# SmartMCU_sch.net
KiCad netlist of a schematic drawn in Altium Designer
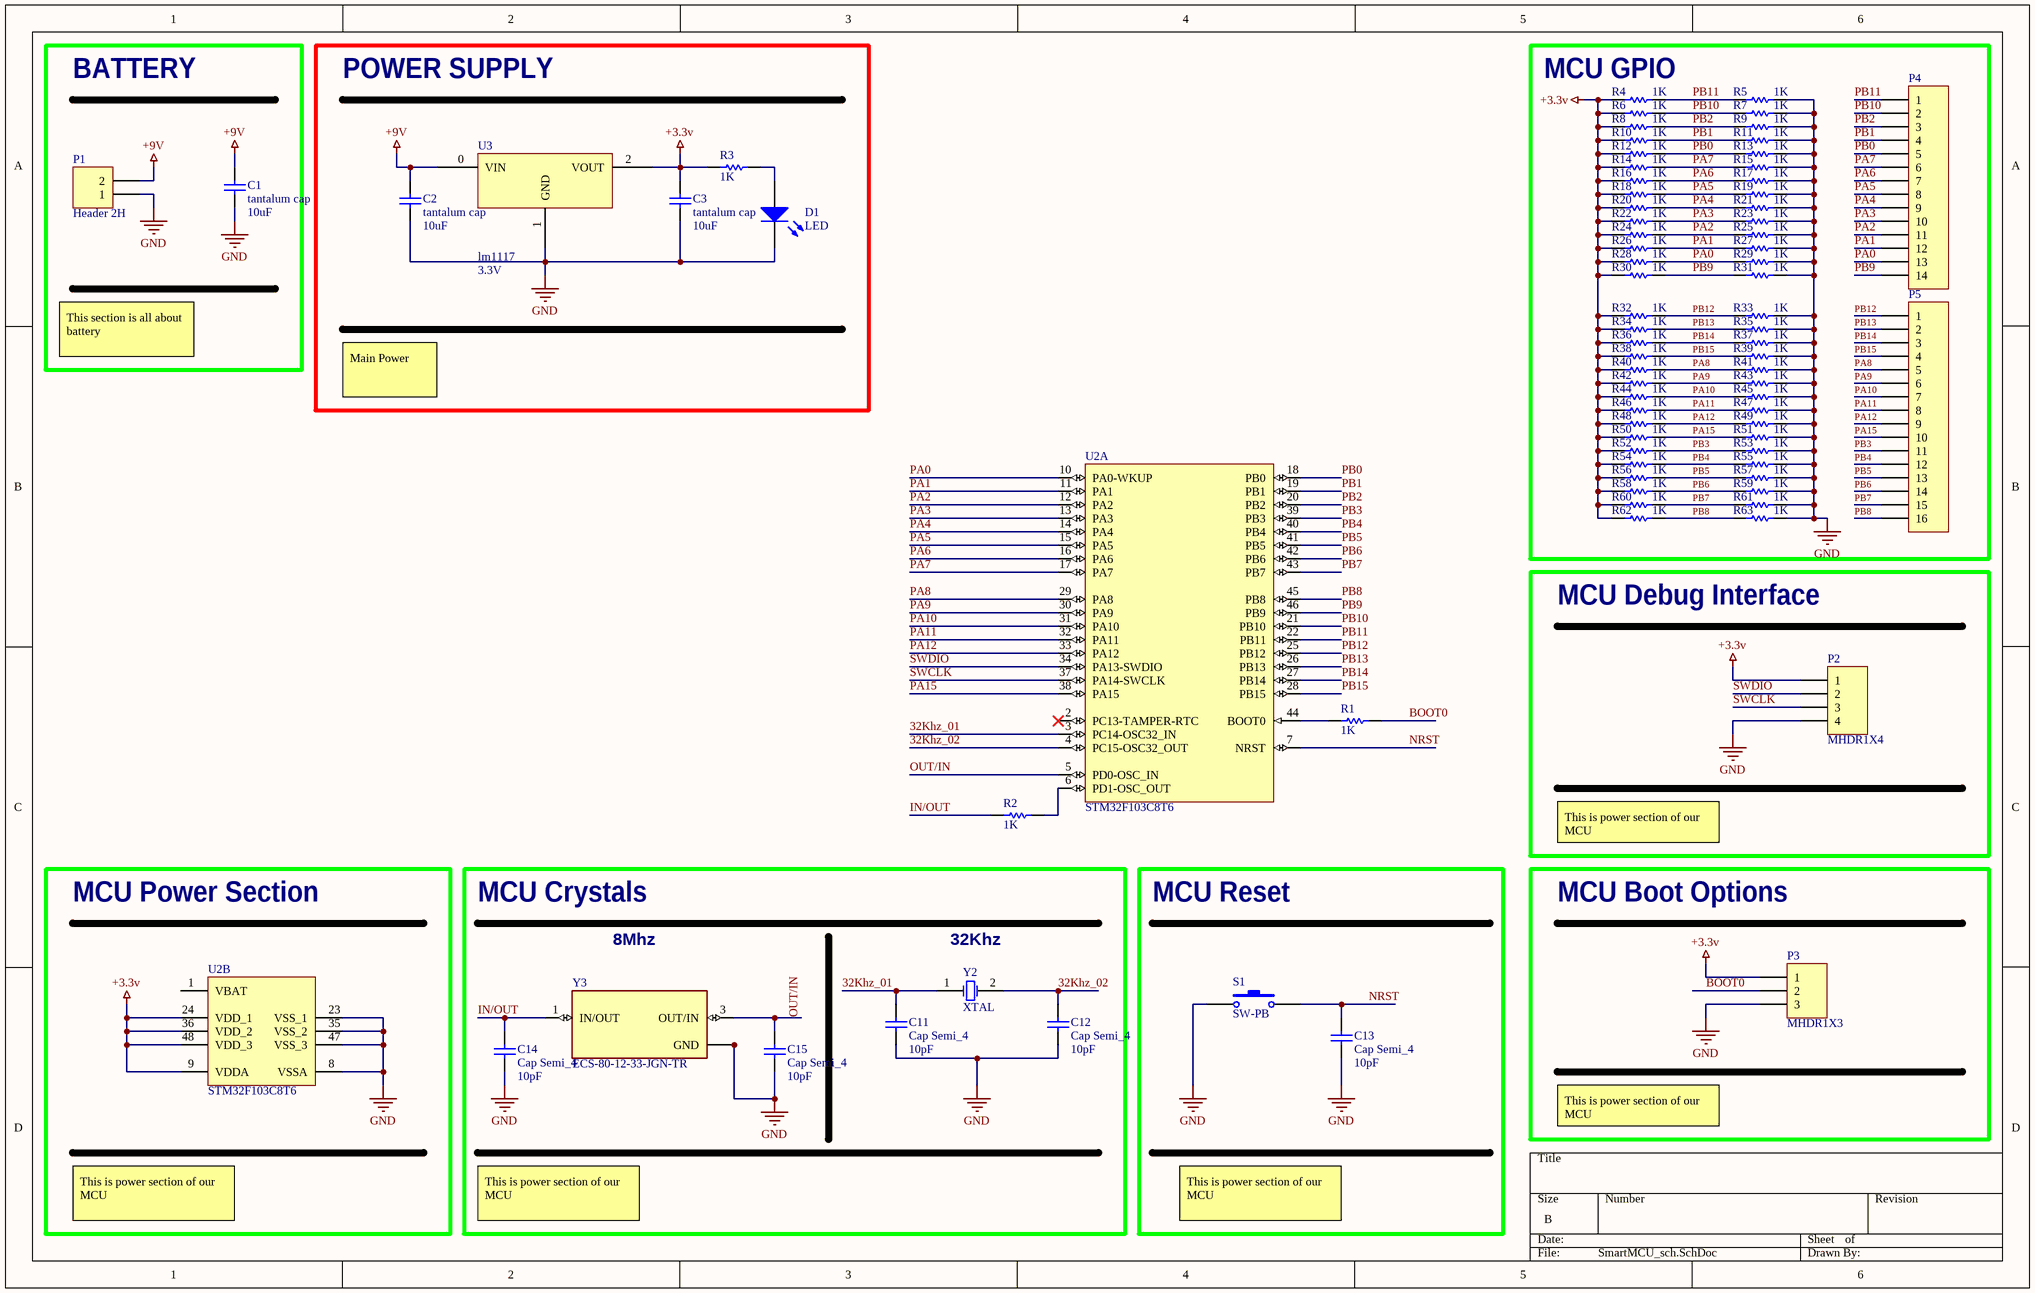
[diagram p0: SmartMCU_sch.SchDoc]

(export (version "E")
  (design (tool "Eeschema 10.0.6"))
  (components
    (comp (ref "C1")
      (value "tantalum cap")
      (footprint "C1206tancap")
      (description "Capacitor (Semiconductor SIM Model)")
      (fields (field (name "ALTIUM_VALUE") "10uF") (field (name "PUBLISHER") "Altium Limited"))
      (libsource (lib "smartmcu") (part "Cap Semi_5"))
    )
    (comp (ref "C2")
      (value "tantalum cap")
      (footprint "C1206tancap")
      (description "Capacitor (Semiconductor SIM Model)")
      (fields (field (name "ALTIUM_VALUE") "10uF") (field (name "PUBLISHER") "Altium Limited"))
      (libsource (lib "smartmcu") (part "Cap Semi_5"))
    )
    (comp (ref "C3")
      (value "tantalum cap")
      (footprint "C1206tancap")
      (description "Capacitor (Semiconductor SIM Model)")
      (fields (field (name "ALTIUM_VALUE") "10uF") (field (name "PUBLISHER") "Altium Limited"))
      (libsource (lib "smartmcu") (part "Cap Semi_5"))
    )
    (comp (ref "C11")
      (value "Cap Semi_4")
      (footprint "0402cap")
      (description "Capacitor (Semiconductor SIM Model)")
      (fields (field (name "ALTIUM_VALUE") "10pF") (field (name "PUBLISHER") "Altium Limited"))
      (libsource (lib "smartmcu") (part "Cap Semi_4"))
    )
    (comp (ref "C12")
      (value "Cap Semi_4")
      (footprint "0402cap")
      (description "Capacitor (Semiconductor SIM Model)")
      (fields (field (name "ALTIUM_VALUE") "10pF") (field (name "PUBLISHER") "Altium Limited"))
      (libsource (lib "smartmcu") (part "Cap Semi_4"))
    )
    (comp (ref "C13")
      (value "Cap Semi_4")
      (footprint "0402cap")
      (description "Capacitor (Semiconductor SIM Model)")
      (fields (field (name "ALTIUM_VALUE") "10pF") (field (name "PUBLISHER") "Altium Limited"))
      (libsource (lib "smartmcu") (part "Cap Semi_4"))
    )
    (comp (ref "C14")
      (value "Cap Semi_4")
      (footprint "0402cap")
      (description "Capacitor (Semiconductor SIM Model)")
      (fields (field (name "ALTIUM_VALUE") "10pF") (field (name "PUBLISHER") "Altium Limited"))
      (libsource (lib "smartmcu") (part "Cap Semi_4"))
    )
    (comp (ref "C15")
      (value "Cap Semi_4")
      (footprint "0402cap")
      (description "Capacitor (Semiconductor SIM Model)")
      (fields (field (name "ALTIUM_VALUE") "10pF") (field (name "PUBLISHER") "Altium Limited"))
      (libsource (lib "smartmcu") (part "Cap Semi_4"))
    )
    (comp (ref "D1")
      (value "LED")
      (footprint "MY_LED_0805")
      (description "Typical INFRARED GaAs LED")
      (fields (field (name "ASID PART NUMBER") "LED-AS"))
      (libsource (lib "Mylib+Rev+4") (part "LED"))
    )
    (comp (ref "P1")
      (value "Header 2H")
      (footprint "HDR1X2H")
      (description "Header, 2-Pin, Right Angle")
      (fields (field (name "VOLTAGE") "9V") (field (name "PUBLISHER") "Altium Limited"))
      (libsource (lib "Miscellaneous Connectors") (part "Header 2H"))
    )
    (comp (ref "P2")
      (value "MHDR1X4")
      (footprint "MHDR1X4body")
      (description "Header, 4-Pin")
      (fields (field (name "PUBLISHER") "Altium Limited"))
      (libsource (lib "smartmcu") (part "MHDR1X4"))
    )
    (comp (ref "P3")
      (value "MHDR1X3")
      (footprint "MHDR1X3body")
      (description "Header, 3-Pin")
      (fields (field (name "PUBLISHER") "Altium Limited"))
      (libsource (lib "smartmcu") (part "MHDR1X3"))
    )
    (comp (ref "P4")
      (value "Header 14")
      (footprint "My_1X14")
      (description "Header, 14-Pin")
      (fields (field (name "ASID PART NUMBER") "Header 14-AS"))
      (libsource (lib "Mylib+Rev+4") (part "Header 14"))
    )
    (comp (ref "P5")
      (value "Header 16")
      (footprint "My_1X16")
      (description "Header, 16-Pin")
      (fields (field (name "ASID PART NUMBER") "Header 16-AS"))
      (libsource (lib "Mylib+Rev+4") (part "Header 16"))
    )
    (comp (ref "R1")
      (value "1K")
      (footprint "MY_0603")
      (description "Standard resistor")
      (fields (field (name "ASID PART NUMBER") "Res-AS"))
      (libsource (lib "Mylib+Rev+4") (part "Res"))
    )
    (comp (ref "R2")
      (value "1K")
      (footprint "MY_0402")
      (description "Standard resistor")
      (fields (field (name "ASID PART NUMBER") "Res-AS"))
      (libsource (lib "Mylib+Rev+4") (part "Res"))
    )
    (comp (ref "R3")
      (value "1K")
      (footprint "MY_0805")
      (description "Standard resistor")
      (fields (field (name "ASID PART NUMBER") "Res-AS"))
      (libsource (lib "Mylib+Rev+4") (part "Res"))
    )
    (comp (ref "R4")
      (value "1K")
      (footprint "MY_0603")
      (description "Standard resistor")
      (fields (field (name "ASID PART NUMBER") "Res-AS"))
      (libsource (lib "Mylib+Rev+4") (part "Res"))
    )
    (comp (ref "R5")
      (value "1K")
      (footprint "MY_0603")
      (description "Standard resistor")
      (fields (field (name "ASID PART NUMBER") "Res-AS"))
      (libsource (lib "Mylib+Rev+4") (part "Res"))
    )
    (comp (ref "R6")
      (value "1K")
      (footprint "MY_0603")
      (description "Standard resistor")
      (fields (field (name "ASID PART NUMBER") "Res-AS"))
      (libsource (lib "Mylib+Rev+4") (part "Res"))
    )
    (comp (ref "R7")
      (value "1K")
      (footprint "MY_0603")
      (description "Standard resistor")
      (fields (field (name "ASID PART NUMBER") "Res-AS"))
      (libsource (lib "Mylib+Rev+4") (part "Res"))
    )
    (comp (ref "R8")
      (value "1K")
      (footprint "MY_0603")
      (description "Standard resistor")
      (fields (field (name "ASID PART NUMBER") "Res-AS"))
      (libsource (lib "Mylib+Rev+4") (part "Res"))
    )
    (comp (ref "R9")
      (value "1K")
      (footprint "MY_0603")
      (description "Standard resistor")
      (fields (field (name "ASID PART NUMBER") "Res-AS"))
      (libsource (lib "Mylib+Rev+4") (part "Res"))
    )
    (comp (ref "R10")
      (value "1K")
      (footprint "MY_0603")
      (description "Standard resistor")
      (fields (field (name "ASID PART NUMBER") "Res-AS"))
      (libsource (lib "Mylib+Rev+4") (part "Res"))
    )
    (comp (ref "R11")
      (value "1K")
      (footprint "MY_0603")
      (description "Standard resistor")
      (fields (field (name "ASID PART NUMBER") "Res-AS"))
      (libsource (lib "Mylib+Rev+4") (part "Res"))
    )
    (comp (ref "R12")
      (value "1K")
      (footprint "MY_0603")
      (description "Standard resistor")
      (fields (field (name "ASID PART NUMBER") "Res-AS"))
      (libsource (lib "Mylib+Rev+4") (part "Res"))
    )
    (comp (ref "R13")
      (value "1K")
      (footprint "MY_0603")
      (description "Standard resistor")
      (fields (field (name "ASID PART NUMBER") "Res-AS"))
      (libsource (lib "Mylib+Rev+4") (part "Res"))
    )
    (comp (ref "R14")
      (value "1K")
      (footprint "MY_0603")
      (description "Standard resistor")
      (fields (field (name "ASID PART NUMBER") "Res-AS"))
      (libsource (lib "Mylib+Rev+4") (part "Res"))
    )
    (comp (ref "R15")
      (value "1K")
      (footprint "MY_0603")
      (description "Standard resistor")
      (fields (field (name "ASID PART NUMBER") "Res-AS"))
      (libsource (lib "Mylib+Rev+4") (part "Res"))
    )
    (comp (ref "R16")
      (value "1K")
      (footprint "MY_0603")
      (description "Standard resistor")
      (fields (field (name "ASID PART NUMBER") "Res-AS"))
      (libsource (lib "Mylib+Rev+4") (part "Res"))
    )
    (comp (ref "R17")
      (value "1K")
      (footprint "MY_0603")
      (description "Standard resistor")
      (fields (field (name "ASID PART NUMBER") "Res-AS"))
      (libsource (lib "Mylib+Rev+4") (part "Res"))
    )
    (comp (ref "R18")
      (value "1K")
      (footprint "MY_0603")
      (description "Standard resistor")
      (fields (field (name "ASID PART NUMBER") "Res-AS"))
      (libsource (lib "Mylib+Rev+4") (part "Res"))
    )
    (comp (ref "R19")
      (value "1K")
      (footprint "MY_0603")
      (description "Standard resistor")
      (fields (field (name "ASID PART NUMBER") "Res-AS"))
      (libsource (lib "Mylib+Rev+4") (part "Res"))
    )
    (comp (ref "R20")
      (value "1K")
      (footprint "MY_0603")
      (description "Standard resistor")
      (fields (field (name "ASID PART NUMBER") "Res-AS"))
      (libsource (lib "Mylib+Rev+4") (part "Res"))
    )
    (comp (ref "R21")
      (value "1K")
      (footprint "MY_0603")
      (description "Standard resistor")
      (fields (field (name "ASID PART NUMBER") "Res-AS"))
      (libsource (lib "Mylib+Rev+4") (part "Res"))
    )
    (comp (ref "R22")
      (value "1K")
      (footprint "MY_0603")
      (description "Standard resistor")
      (fields (field (name "ASID PART NUMBER") "Res-AS"))
      (libsource (lib "Mylib+Rev+4") (part "Res"))
    )
    (comp (ref "R23")
      (value "1K")
      (footprint "MY_0603")
      (description "Standard resistor")
      (fields (field (name "ASID PART NUMBER") "Res-AS"))
      (libsource (lib "Mylib+Rev+4") (part "Res"))
    )
    (comp (ref "R24")
      (value "1K")
      (footprint "MY_0603")
      (description "Standard resistor")
      (fields (field (name "ASID PART NUMBER") "Res-AS"))
      (libsource (lib "Mylib+Rev+4") (part "Res"))
    )
    (comp (ref "R25")
      (value "1K")
      (footprint "MY_0603")
      (description "Standard resistor")
      (fields (field (name "ASID PART NUMBER") "Res-AS"))
      (libsource (lib "Mylib+Rev+4") (part "Res"))
    )
    (comp (ref "R26")
      (value "1K")
      (footprint "MY_0603")
      (description "Standard resistor")
      (fields (field (name "ASID PART NUMBER") "Res-AS"))
      (libsource (lib "Mylib+Rev+4") (part "Res"))
    )
    (comp (ref "R27")
      (value "1K")
      (footprint "MY_0603")
      (description "Standard resistor")
      (fields (field (name "ASID PART NUMBER") "Res-AS"))
      (libsource (lib "Mylib+Rev+4") (part "Res"))
    )
    (comp (ref "R28")
      (value "1K")
      (footprint "MY_0603")
      (description "Standard resistor")
      (fields (field (name "ASID PART NUMBER") "Res-AS"))
      (libsource (lib "Mylib+Rev+4") (part "Res"))
    )
    (comp (ref "R29")
      (value "1K")
      (footprint "MY_0603")
      (description "Standard resistor")
      (fields (field (name "ASID PART NUMBER") "Res-AS"))
      (libsource (lib "Mylib+Rev+4") (part "Res"))
    )
    (comp (ref "R30")
      (value "1K")
      (footprint "MY_0603")
      (description "Standard resistor")
      (fields (field (name "ASID PART NUMBER") "Res-AS"))
      (libsource (lib "Mylib+Rev+4") (part "Res"))
    )
    (comp (ref "R31")
      (value "1K")
      (footprint "MY_0603")
      (description "Standard resistor")
      (fields (field (name "ASID PART NUMBER") "Res-AS"))
      (libsource (lib "Mylib+Rev+4") (part "Res"))
    )
    (comp (ref "R32")
      (value "1K")
      (footprint "MY_0603")
      (description "Standard resistor")
      (fields (field (name "ASID PART NUMBER") "Res-AS"))
      (libsource (lib "Mylib+Rev+4") (part "Res"))
    )
    (comp (ref "R33")
      (value "1K")
      (footprint "MY_0603")
      (description "Standard resistor")
      (fields (field (name "ASID PART NUMBER") "Res-AS"))
      (libsource (lib "Mylib+Rev+4") (part "Res"))
    )
    (comp (ref "R34")
      (value "1K")
      (footprint "MY_0603")
      (description "Standard resistor")
      (fields (field (name "ASID PART NUMBER") "Res-AS"))
      (libsource (lib "Mylib+Rev+4") (part "Res"))
    )
    (comp (ref "R35")
      (value "1K")
      (footprint "MY_0603")
      (description "Standard resistor")
      (fields (field (name "ASID PART NUMBER") "Res-AS"))
      (libsource (lib "Mylib+Rev+4") (part "Res"))
    )
    (comp (ref "R36")
      (value "1K")
      (footprint "MY_0603")
      (description "Standard resistor")
      (fields (field (name "ASID PART NUMBER") "Res-AS"))
      (libsource (lib "Mylib+Rev+4") (part "Res"))
    )
    (comp (ref "R37")
      (value "1K")
      (footprint "MY_0603")
      (description "Standard resistor")
      (fields (field (name "ASID PART NUMBER") "Res-AS"))
      (libsource (lib "Mylib+Rev+4") (part "Res"))
    )
    (comp (ref "R38")
      (value "1K")
      (footprint "MY_0603")
      (description "Standard resistor")
      (fields (field (name "ASID PART NUMBER") "Res-AS"))
      (libsource (lib "Mylib+Rev+4") (part "Res"))
    )
    (comp (ref "R39")
      (value "1K")
      (footprint "MY_0603")
      (description "Standard resistor")
      (fields (field (name "ASID PART NUMBER") "Res-AS"))
      (libsource (lib "Mylib+Rev+4") (part "Res"))
    )
    (comp (ref "R40")
      (value "1K")
      (footprint "MY_0603")
      (description "Standard resistor")
      (fields (field (name "ASID PART NUMBER") "Res-AS"))
      (libsource (lib "Mylib+Rev+4") (part "Res"))
    )
    (comp (ref "R41")
      (value "1K")
      (footprint "MY_0603")
      (description "Standard resistor")
      (fields (field (name "ASID PART NUMBER") "Res-AS"))
      (libsource (lib "Mylib+Rev+4") (part "Res"))
    )
    (comp (ref "R42")
      (value "1K")
      (footprint "MY_0603")
      (description "Standard resistor")
      (fields (field (name "ASID PART NUMBER") "Res-AS"))
      (libsource (lib "Mylib+Rev+4") (part "Res"))
    )
    (comp (ref "R43")
      (value "1K")
      (footprint "MY_0603")
      (description "Standard resistor")
      (fields (field (name "ASID PART NUMBER") "Res-AS"))
      (libsource (lib "Mylib+Rev+4") (part "Res"))
    )
    (comp (ref "R44")
      (value "1K")
      (footprint "MY_0603")
      (description "Standard resistor")
      (fields (field (name "ASID PART NUMBER") "Res-AS"))
      (libsource (lib "Mylib+Rev+4") (part "Res"))
    )
    (comp (ref "R45")
      (value "1K")
      (footprint "MY_0603")
      (description "Standard resistor")
      (fields (field (name "ASID PART NUMBER") "Res-AS"))
      (libsource (lib "Mylib+Rev+4") (part "Res"))
    )
    (comp (ref "R46")
      (value "1K")
      (footprint "MY_0603")
      (description "Standard resistor")
      (fields (field (name "ASID PART NUMBER") "Res-AS"))
      (libsource (lib "Mylib+Rev+4") (part "Res"))
    )
    (comp (ref "R47")
      (value "1K")
      (footprint "MY_0603")
      (description "Standard resistor")
      (fields (field (name "ASID PART NUMBER") "Res-AS"))
      (libsource (lib "Mylib+Rev+4") (part "Res"))
    )
    (comp (ref "R48")
      (value "1K")
      (footprint "MY_0603")
      (description "Standard resistor")
      (fields (field (name "ASID PART NUMBER") "Res-AS"))
      (libsource (lib "Mylib+Rev+4") (part "Res"))
    )
    (comp (ref "R49")
      (value "1K")
      (footprint "MY_0603")
      (description "Standard resistor")
      (fields (field (name "ASID PART NUMBER") "Res-AS"))
      (libsource (lib "Mylib+Rev+4") (part "Res"))
    )
    (comp (ref "R50")
      (value "1K")
      (footprint "MY_0603")
      (description "Standard resistor")
      (fields (field (name "ASID PART NUMBER") "Res-AS"))
      (libsource (lib "Mylib+Rev+4") (part "Res"))
    )
    (comp (ref "R51")
      (value "1K")
      (footprint "MY_0603")
      (description "Standard resistor")
      (fields (field (name "ASID PART NUMBER") "Res-AS"))
      (libsource (lib "Mylib+Rev+4") (part "Res"))
    )
    (comp (ref "R52")
      (value "1K")
      (footprint "MY_0603")
      (description "Standard resistor")
      (fields (field (name "ASID PART NUMBER") "Res-AS"))
      (libsource (lib "Mylib+Rev+4") (part "Res"))
    )
    (comp (ref "R53")
      (value "1K")
      (footprint "MY_0603")
      (description "Standard resistor")
      (fields (field (name "ASID PART NUMBER") "Res-AS"))
      (libsource (lib "Mylib+Rev+4") (part "Res"))
    )
    (comp (ref "R54")
      (value "1K")
      (footprint "MY_0603")
      (description "Standard resistor")
      (fields (field (name "ASID PART NUMBER") "Res-AS"))
      (libsource (lib "Mylib+Rev+4") (part "Res"))
    )
    (comp (ref "R55")
      (value "1K")
      (footprint "MY_0603")
      (description "Standard resistor")
      (fields (field (name "ASID PART NUMBER") "Res-AS"))
      (libsource (lib "Mylib+Rev+4") (part "Res"))
    )
    (comp (ref "R56")
      (value "1K")
      (footprint "MY_0603")
      (description "Standard resistor")
      (fields (field (name "ASID PART NUMBER") "Res-AS"))
      (libsource (lib "Mylib+Rev+4") (part "Res"))
    )
    (comp (ref "R57")
      (value "1K")
      (footprint "MY_0603")
      (description "Standard resistor")
      (fields (field (name "ASID PART NUMBER") "Res-AS"))
      (libsource (lib "Mylib+Rev+4") (part "Res"))
    )
    (comp (ref "R58")
      (value "1K")
      (footprint "MY_0603")
      (description "Standard resistor")
      (fields (field (name "ASID PART NUMBER") "Res-AS"))
      (libsource (lib "Mylib+Rev+4") (part "Res"))
    )
    (comp (ref "R59")
      (value "1K")
      (footprint "MY_0603")
      (description "Standard resistor")
      (fields (field (name "ASID PART NUMBER") "Res-AS"))
      (libsource (lib "Mylib+Rev+4") (part "Res"))
    )
    (comp (ref "R60")
      (value "1K")
      (footprint "MY_0603")
      (description "Standard resistor")
      (fields (field (name "ASID PART NUMBER") "Res-AS"))
      (libsource (lib "Mylib+Rev+4") (part "Res"))
    )
    (comp (ref "R61")
      (value "1K")
      (footprint "MY_0603")
      (description "Standard resistor")
      (fields (field (name "ASID PART NUMBER") "Res-AS"))
      (libsource (lib "Mylib+Rev+4") (part "Res"))
    )
    (comp (ref "R62")
      (value "1K")
      (footprint "MY_0603")
      (description "Standard resistor")
      (fields (field (name "ASID PART NUMBER") "Res-AS"))
      (libsource (lib "Mylib+Rev+4") (part "Res"))
    )
    (comp (ref "R63")
      (value "1K")
      (footprint "MY_0603")
      (description "Standard resistor")
      (fields (field (name "ASID PART NUMBER") "Res-AS"))
      (libsource (lib "Mylib+Rev+4") (part "Res"))
    )
    (comp (ref "S1")
      (value "SW-PB")
      (footprint "SPST-2_body")
      (description "Switch")
      (fields (field (name "PUBLISHER") "Altium Limited"))
      (libsource (lib "smartmcu") (part "SW-PB"))
    )
    (comp (ref "U2")
      (value "STM32F103C8T6")
      (footprint "STM-LQFP48_L")
      (libsource (lib "Altium Content Vault") (part "MC-ARM-STM32F103X8_B-SQ48"))
    )
    (comp (ref "U3")
      (value "lm1117")
      (footprint "4-Pin SOT")
      (fields (field (name "OUTPUT VOLTAG") "3.3V"))
      (libsource (lib "smartmcu") (part "lm1117"))
    )
    (comp (ref "Y2")
      (value "XTAL")
      (footprint "32768")
      (description "Crystal Oscillator")
      (fields (field (name "PUBLISHER") "Altium Limited"))
      (libsource (lib "smartmcu") (part "XTAL"))
    )
    (comp (ref "Y3")
      (value "ECS-80-12-33-JGN-TR")
      (footprint "8MHZCrystall")
      (description "8MHz Â±20ppm Crystal 12pF 400 Ohms 4-SMD, No Lead")
      (fields
        (field (name "MF") "ECS Inc.")
        (field (name "BUYPART") "https://www.snapeda.com/parts/ECS-80-12-33-JGN-TR/ECS%20Inc./view-part/4477300/?ref=eda")
      )
      (libsource (lib "smartmcu") (part "ECS-80-12-33-JGN-TR"))
    )
  )
  (nets
    (net (code "1") (name "+3.3v") (class "Default")
      (node (ref "C3") (pin "2") (pinfunction "2_2") (pintype "passive"))
      (node (ref "P2") (pin "1") (pinfunction "1_1") (pintype "passive"))
      (node (ref "P3") (pin "1") (pinfunction "1_1") (pintype "passive"))
      (node (ref "R10") (pin "1") (pinfunction "1_1") (pintype "passive"))
      (node (ref "R12") (pin "1") (pinfunction "1_1") (pintype "passive"))
      (node (ref "R14") (pin "1") (pinfunction "1_1") (pintype "passive"))
      (node (ref "R16") (pin "1") (pinfunction "1_1") (pintype "passive"))
      (node (ref "R18") (pin "1") (pinfunction "1_1") (pintype "passive"))
      (node (ref "R20") (pin "1") (pinfunction "1_1") (pintype "passive"))
      (node (ref "R22") (pin "1") (pinfunction "1_1") (pintype "passive"))
      (node (ref "R24") (pin "1") (pinfunction "1_1") (pintype "passive"))
      (node (ref "R26") (pin "1") (pinfunction "1_1") (pintype "passive"))
      (node (ref "R28") (pin "1") (pinfunction "1_1") (pintype "passive"))
      (node (ref "R3") (pin "1") (pinfunction "1_1") (pintype "passive"))
      (node (ref "R30") (pin "1") (pinfunction "1_1") (pintype "passive"))
      (node (ref "R32") (pin "1") (pinfunction "1_1") (pintype "passive"))
      (node (ref "R34") (pin "1") (pinfunction "1_1") (pintype "passive"))
      (node (ref "R36") (pin "1") (pinfunction "1_1") (pintype "passive"))
      (node (ref "R38") (pin "1") (pinfunction "1_1") (pintype "passive"))
      (node (ref "R4") (pin "1") (pinfunction "1_1") (pintype "passive"))
      (node (ref "R40") (pin "1") (pinfunction "1_1") (pintype "passive"))
      (node (ref "R42") (pin "1") (pinfunction "1_1") (pintype "passive"))
      (node (ref "R44") (pin "1") (pinfunction "1_1") (pintype "passive"))
      (node (ref "R46") (pin "1") (pinfunction "1_1") (pintype "passive"))
      (node (ref "R48") (pin "1") (pinfunction "1_1") (pintype "passive"))
      (node (ref "R50") (pin "1") (pinfunction "1_1") (pintype "passive"))
      (node (ref "R52") (pin "1") (pinfunction "1_1") (pintype "passive"))
      (node (ref "R54") (pin "1") (pinfunction "1_1") (pintype "passive"))
      (node (ref "R56") (pin "1") (pinfunction "1_1") (pintype "passive"))
      (node (ref "R58") (pin "1") (pinfunction "1_1") (pintype "passive"))
      (node (ref "R6") (pin "1") (pinfunction "1_1") (pintype "passive"))
      (node (ref "R60") (pin "1") (pinfunction "1_1") (pintype "passive"))
      (node (ref "R62") (pin "1") (pinfunction "1_1") (pintype "passive"))
      (node (ref "R8") (pin "1") (pinfunction "1_1") (pintype "passive"))
      (node (ref "U2") (pin "24") (pinfunction "VDD_1_24") (pintype "power_in"))
      (node (ref "U2") (pin "36") (pinfunction "VDD_2_36") (pintype "power_in"))
      (node (ref "U2") (pin "48") (pinfunction "VDD_3_48") (pintype "power_in"))
      (node (ref "U2") (pin "9") (pinfunction "VDDA_9") (pintype "power_in"))
      (node (ref "U3") (pin "2") (pinfunction "VOUT_2") (pintype "passive"))
    )
    (net (code "2") (name "+9V") (class "Default")
      (node (ref "C1") (pin "2") (pinfunction "2_2") (pintype "passive"))
      (node (ref "C2") (pin "2") (pinfunction "2_2") (pintype "passive"))
      (node (ref "P1") (pin "2") (pinfunction "2_2") (pintype "passive"))
      (node (ref "U3") (pin "0") (pinfunction "VIN_0") (pintype "passive"))
    )
    (net (code "3") (name "/32Khz_01") (class "Default")
      (node (ref "C11") (pin "1") (pinfunction "1_1") (pintype "passive"))
      (node (ref "U2") (pin "3") (pinfunction "PC14-OSC32_IN_3") (pintype "bidirectional"))
      (node (ref "Y2") (pin "1") (pinfunction "OSC1_1") (pintype "passive"))
    )
    (net (code "4") (name "/32Khz_02") (class "Default")
      (node (ref "C12") (pin "1") (pinfunction "1_1") (pintype "passive"))
      (node (ref "U2") (pin "4") (pinfunction "PC15-OSC32_OUT_4") (pintype "bidirectional"))
      (node (ref "Y2") (pin "2") (pinfunction "OSC2_2") (pintype "passive"))
    )
    (net (code "5") (name "/BOOT0") (class "Default")
      (node (ref "P3") (pin "2") (pinfunction "2_2") (pintype "passive"))
      (node (ref "R1") (pin "2") (pinfunction "2_2") (pintype "passive"))
    )
    (net (code "6") (name "/IN{slash}OUT") (class "Default")
      (node (ref "C14") (pin "1") (pinfunction "1_1") (pintype "passive"))
      (node (ref "R2") (pin "1") (pinfunction "1_1") (pintype "passive"))
      (node (ref "Y3") (pin "1") (pinfunction "IN/OUT_1") (pintype "bidirectional"))
    )
    (net (code "7") (name "/NRST") (class "Default")
      (node (ref "C13") (pin "2") (pinfunction "2_2") (pintype "passive"))
      (node (ref "S1") (pin "2") (pinfunction "2_2") (pintype "passive"))
      (node (ref "U2") (pin "7") (pinfunction "NRST_7") (pintype "bidirectional"))
    )
    (net (code "8") (name "/OUT{slash}IN") (class "Default")
      (node (ref "C15") (pin "1") (pinfunction "1_1") (pintype "passive"))
      (node (ref "U2") (pin "5") (pinfunction "PD0-OSC_IN_5") (pintype "bidirectional"))
      (node (ref "Y3") (pin "3") (pinfunction "OUT/IN_3") (pintype "bidirectional"))
    )
    (net (code "9") (name "/PA0") (class "Default")
      (node (ref "P4") (pin "13") (pinfunction "13_13") (pintype "passive"))
      (node (ref "R28") (pin "2") (pinfunction "2_2") (pintype "passive"))
      (node (ref "R29") (pin "1") (pinfunction "1_1") (pintype "passive"))
      (node (ref "U2") (pin "10") (pinfunction "PA0-WKUP_10") (pintype "bidirectional"))
    )
    (net (code "10") (name "/PA1") (class "Default")
      (node (ref "P4") (pin "12") (pinfunction "12_12") (pintype "passive"))
      (node (ref "R26") (pin "2") (pinfunction "2_2") (pintype "passive"))
      (node (ref "R27") (pin "1") (pinfunction "1_1") (pintype "passive"))
      (node (ref "U2") (pin "11") (pinfunction "PA1_11") (pintype "bidirectional"))
    )
    (net (code "11") (name "/PA2") (class "Default")
      (node (ref "P4") (pin "11") (pinfunction "11_11") (pintype "passive"))
      (node (ref "R24") (pin "2") (pinfunction "2_2") (pintype "passive"))
      (node (ref "R25") (pin "1") (pinfunction "1_1") (pintype "passive"))
      (node (ref "U2") (pin "12") (pinfunction "PA2_12") (pintype "bidirectional"))
    )
    (net (code "12") (name "/PA3") (class "Default")
      (node (ref "P4") (pin "10") (pinfunction "10_10") (pintype "passive"))
      (node (ref "R22") (pin "2") (pinfunction "2_2") (pintype "passive"))
      (node (ref "R23") (pin "1") (pinfunction "1_1") (pintype "passive"))
      (node (ref "U2") (pin "13") (pinfunction "PA3_13") (pintype "bidirectional"))
    )
    (net (code "13") (name "/PA4") (class "Default")
      (node (ref "P4") (pin "9") (pinfunction "9_9") (pintype "passive"))
      (node (ref "R20") (pin "2") (pinfunction "2_2") (pintype "passive"))
      (node (ref "R21") (pin "1") (pinfunction "1_1") (pintype "passive"))
      (node (ref "U2") (pin "14") (pinfunction "PA4_14") (pintype "bidirectional"))
    )
    (net (code "14") (name "/PA5") (class "Default")
      (node (ref "P4") (pin "8") (pinfunction "8_8") (pintype "passive"))
      (node (ref "R18") (pin "2") (pinfunction "2_2") (pintype "passive"))
      (node (ref "R19") (pin "1") (pinfunction "1_1") (pintype "passive"))
      (node (ref "U2") (pin "15") (pinfunction "PA5_15") (pintype "bidirectional"))
    )
    (net (code "15") (name "/PA6") (class "Default")
      (node (ref "P4") (pin "7") (pinfunction "7_7") (pintype "passive"))
      (node (ref "R16") (pin "2") (pinfunction "2_2") (pintype "passive"))
      (node (ref "R17") (pin "1") (pinfunction "1_1") (pintype "passive"))
      (node (ref "U2") (pin "16") (pinfunction "PA6_16") (pintype "bidirectional"))
    )
    (net (code "16") (name "/PA7") (class "Default")
      (node (ref "P4") (pin "6") (pinfunction "6_6") (pintype "passive"))
      (node (ref "R14") (pin "2") (pinfunction "2_2") (pintype "passive"))
      (node (ref "R15") (pin "1") (pinfunction "1_1") (pintype "passive"))
      (node (ref "U2") (pin "17") (pinfunction "PA7_17") (pintype "bidirectional"))
    )
    (net (code "17") (name "/PA8") (class "Default")
      (node (ref "P5") (pin "5") (pinfunction "5_5") (pintype "passive"))
      (node (ref "R40") (pin "2") (pinfunction "2_2") (pintype "passive"))
      (node (ref "R41") (pin "1") (pinfunction "1_1") (pintype "passive"))
      (node (ref "U2") (pin "29") (pinfunction "PA8_29") (pintype "bidirectional"))
    )
    (net (code "18") (name "/PA9") (class "Default")
      (node (ref "P5") (pin "6") (pinfunction "6_6") (pintype "passive"))
      (node (ref "R42") (pin "2") (pinfunction "2_2") (pintype "passive"))
      (node (ref "R43") (pin "1") (pinfunction "1_1") (pintype "passive"))
      (node (ref "U2") (pin "30") (pinfunction "PA9_30") (pintype "bidirectional"))
    )
    (net (code "19") (name "/PA10") (class "Default")
      (node (ref "P5") (pin "7") (pinfunction "7_7") (pintype "passive"))
      (node (ref "R44") (pin "2") (pinfunction "2_2") (pintype "passive"))
      (node (ref "R45") (pin "1") (pinfunction "1_1") (pintype "passive"))
      (node (ref "U2") (pin "31") (pinfunction "PA10_31") (pintype "bidirectional"))
    )
    (net (code "20") (name "/PA11") (class "Default")
      (node (ref "P5") (pin "8") (pinfunction "8_8") (pintype "passive"))
      (node (ref "R46") (pin "2") (pinfunction "2_2") (pintype "passive"))
      (node (ref "R47") (pin "1") (pinfunction "1_1") (pintype "passive"))
      (node (ref "U2") (pin "32") (pinfunction "PA11_32") (pintype "bidirectional"))
    )
    (net (code "21") (name "/PA12") (class "Default")
      (node (ref "P5") (pin "9") (pinfunction "9_9") (pintype "passive"))
      (node (ref "R48") (pin "2") (pinfunction "2_2") (pintype "passive"))
      (node (ref "R49") (pin "1") (pinfunction "1_1") (pintype "passive"))
      (node (ref "U2") (pin "33") (pinfunction "PA12_33") (pintype "bidirectional"))
    )
    (net (code "22") (name "/PA15") (class "Default")
      (node (ref "P5") (pin "10") (pinfunction "10_10") (pintype "passive"))
      (node (ref "R50") (pin "2") (pinfunction "2_2") (pintype "passive"))
      (node (ref "R51") (pin "1") (pinfunction "1_1") (pintype "passive"))
      (node (ref "U2") (pin "38") (pinfunction "PA15_38") (pintype "bidirectional"))
    )
    (net (code "23") (name "/PB0") (class "Default")
      (node (ref "P4") (pin "5") (pinfunction "5_5") (pintype "passive"))
      (node (ref "R12") (pin "2") (pinfunction "2_2") (pintype "passive"))
      (node (ref "R13") (pin "1") (pinfunction "1_1") (pintype "passive"))
      (node (ref "U2") (pin "18") (pinfunction "PB0_18") (pintype "bidirectional"))
    )
    (net (code "24") (name "/PB1") (class "Default")
      (node (ref "P4") (pin "4") (pinfunction "4_4") (pintype "passive"))
      (node (ref "R10") (pin "2") (pinfunction "2_2") (pintype "passive"))
      (node (ref "R11") (pin "1") (pinfunction "1_1") (pintype "passive"))
      (node (ref "U2") (pin "19") (pinfunction "PB1_19") (pintype "bidirectional"))
    )
    (net (code "25") (name "/PB2") (class "Default")
      (node (ref "P4") (pin "3") (pinfunction "3_3") (pintype "passive"))
      (node (ref "R8") (pin "2") (pinfunction "2_2") (pintype "passive"))
      (node (ref "R9") (pin "1") (pinfunction "1_1") (pintype "passive"))
      (node (ref "U2") (pin "20") (pinfunction "PB2_20") (pintype "bidirectional"))
    )
    (net (code "26") (name "/PB3") (class "Default")
      (node (ref "P5") (pin "11") (pinfunction "11_11") (pintype "passive"))
      (node (ref "R52") (pin "2") (pinfunction "2_2") (pintype "passive"))
      (node (ref "R53") (pin "1") (pinfunction "1_1") (pintype "passive"))
      (node (ref "U2") (pin "39") (pinfunction "PB3_39") (pintype "bidirectional"))
    )
    (net (code "27") (name "/PB4") (class "Default")
      (node (ref "P5") (pin "12") (pinfunction "12_12") (pintype "passive"))
      (node (ref "R54") (pin "2") (pinfunction "2_2") (pintype "passive"))
      (node (ref "R55") (pin "1") (pinfunction "1_1") (pintype "passive"))
      (node (ref "U2") (pin "40") (pinfunction "PB4_40") (pintype "bidirectional"))
    )
    (net (code "28") (name "/PB5") (class "Default")
      (node (ref "P5") (pin "13") (pinfunction "13_13") (pintype "passive"))
      (node (ref "R56") (pin "2") (pinfunction "2_2") (pintype "passive"))
      (node (ref "R57") (pin "1") (pinfunction "1_1") (pintype "passive"))
      (node (ref "U2") (pin "41") (pinfunction "PB5_41") (pintype "bidirectional"))
    )
    (net (code "29") (name "/PB6") (class "Default")
      (node (ref "P5") (pin "14") (pinfunction "14_14") (pintype "passive"))
      (node (ref "R58") (pin "2") (pinfunction "2_2") (pintype "passive"))
      (node (ref "R59") (pin "1") (pinfunction "1_1") (pintype "passive"))
      (node (ref "U2") (pin "42") (pinfunction "PB6_42") (pintype "bidirectional"))
    )
    (net (code "30") (name "/PB7") (class "Default")
      (node (ref "P5") (pin "15") (pinfunction "15_15") (pintype "passive"))
      (node (ref "R60") (pin "2") (pinfunction "2_2") (pintype "passive"))
      (node (ref "R61") (pin "1") (pinfunction "1_1") (pintype "passive"))
      (node (ref "U2") (pin "43") (pinfunction "PB7_43") (pintype "bidirectional"))
    )
    (net (code "31") (name "/PB8") (class "Default")
      (node (ref "P5") (pin "16") (pinfunction "16_16") (pintype "passive"))
      (node (ref "R62") (pin "2") (pinfunction "2_2") (pintype "passive"))
      (node (ref "R63") (pin "1") (pinfunction "1_1") (pintype "passive"))
      (node (ref "U2") (pin "45") (pinfunction "PB8_45") (pintype "bidirectional"))
    )
    (net (code "32") (name "/PB9") (class "Default")
      (node (ref "P4") (pin "14") (pinfunction "14_14") (pintype "passive"))
      (node (ref "R30") (pin "2") (pinfunction "2_2") (pintype "passive"))
      (node (ref "R31") (pin "1") (pinfunction "1_1") (pintype "passive"))
      (node (ref "U2") (pin "46") (pinfunction "PB9_46") (pintype "bidirectional"))
    )
    (net (code "33") (name "/PB10") (class "Default")
      (node (ref "P4") (pin "2") (pinfunction "2_2") (pintype "passive"))
      (node (ref "R6") (pin "2") (pinfunction "2_2") (pintype "passive"))
      (node (ref "R7") (pin "1") (pinfunction "1_1") (pintype "passive"))
      (node (ref "U2") (pin "21") (pinfunction "PB10_21") (pintype "bidirectional"))
    )
    (net (code "34") (name "/PB11") (class "Default")
      (node (ref "P4") (pin "1") (pinfunction "1_1") (pintype "passive"))
      (node (ref "R4") (pin "2") (pinfunction "2_2") (pintype "passive"))
      (node (ref "R5") (pin "1") (pinfunction "1_1") (pintype "passive"))
      (node (ref "U2") (pin "22") (pinfunction "PB11_22") (pintype "bidirectional"))
    )
    (net (code "35") (name "/PB12") (class "Default")
      (node (ref "P5") (pin "1") (pinfunction "1_1") (pintype "passive"))
      (node (ref "R32") (pin "2") (pinfunction "2_2") (pintype "passive"))
      (node (ref "R33") (pin "1") (pinfunction "1_1") (pintype "passive"))
      (node (ref "U2") (pin "25") (pinfunction "PB12_25") (pintype "bidirectional"))
    )
    (net (code "36") (name "/PB13") (class "Default")
      (node (ref "P5") (pin "2") (pinfunction "2_2") (pintype "passive"))
      (node (ref "R34") (pin "2") (pinfunction "2_2") (pintype "passive"))
      (node (ref "R35") (pin "1") (pinfunction "1_1") (pintype "passive"))
      (node (ref "U2") (pin "26") (pinfunction "PB13_26") (pintype "bidirectional"))
    )
    (net (code "37") (name "/PB14") (class "Default")
      (node (ref "P5") (pin "3") (pinfunction "3_3") (pintype "passive"))
      (node (ref "R36") (pin "2") (pinfunction "2_2") (pintype "passive"))
      (node (ref "R37") (pin "1") (pinfunction "1_1") (pintype "passive"))
      (node (ref "U2") (pin "27") (pinfunction "PB14_27") (pintype "bidirectional"))
    )
    (net (code "38") (name "/PB15") (class "Default")
      (node (ref "P5") (pin "4") (pinfunction "4_4") (pintype "passive"))
      (node (ref "R38") (pin "2") (pinfunction "2_2") (pintype "passive"))
      (node (ref "R39") (pin "1") (pinfunction "1_1") (pintype "passive"))
      (node (ref "U2") (pin "28") (pinfunction "PB15_28") (pintype "bidirectional"))
    )
    (net (code "39") (name "/SWCLK") (class "Default")
      (node (ref "P2") (pin "3") (pinfunction "3_3") (pintype "passive"))
      (node (ref "U2") (pin "37") (pinfunction "PA14_37") (pintype "bidirectional"))
    )
    (net (code "40") (name "/SWDIO") (class "Default")
      (node (ref "P2") (pin "2") (pinfunction "2_2") (pintype "passive"))
      (node (ref "U2") (pin "34") (pinfunction "PA13_34") (pintype "bidirectional"))
    )
    (net (code "41") (name "GND") (class "Default")
      (node (ref "C1") (pin "1") (pinfunction "1_1") (pintype "passive"))
      (node (ref "C11") (pin "2") (pinfunction "2_2") (pintype "passive"))
      (node (ref "C12") (pin "2") (pinfunction "2_2") (pintype "passive"))
      (node (ref "C13") (pin "1") (pinfunction "1_1") (pintype "passive"))
      (node (ref "C14") (pin "2") (pinfunction "2_2") (pintype "passive"))
      (node (ref "C15") (pin "2") (pinfunction "2_2") (pintype "passive"))
      (node (ref "C2") (pin "1") (pinfunction "1_1") (pintype "passive"))
      (node (ref "C3") (pin "1") (pinfunction "1_1") (pintype "passive"))
      (node (ref "D1") (pin "K") (pinfunction "K_K") (pintype "passive"))
      (node (ref "P1") (pin "1") (pinfunction "1_1") (pintype "passive"))
      (node (ref "P2") (pin "4") (pinfunction "4_4") (pintype "passive"))
      (node (ref "P3") (pin "3") (pinfunction "3_3") (pintype "passive"))
      (node (ref "R11") (pin "2") (pinfunction "2_2") (pintype "passive"))
      (node (ref "R13") (pin "2") (pinfunction "2_2") (pintype "passive"))
      (node (ref "R15") (pin "2") (pinfunction "2_2") (pintype "passive"))
      (node (ref "R17") (pin "2") (pinfunction "2_2") (pintype "passive"))
      (node (ref "R19") (pin "2") (pinfunction "2_2") (pintype "passive"))
      (node (ref "R21") (pin "2") (pinfunction "2_2") (pintype "passive"))
      (node (ref "R23") (pin "2") (pinfunction "2_2") (pintype "passive"))
      (node (ref "R25") (pin "2") (pinfunction "2_2") (pintype "passive"))
      (node (ref "R27") (pin "2") (pinfunction "2_2") (pintype "passive"))
      (node (ref "R29") (pin "2") (pinfunction "2_2") (pintype "passive"))
      (node (ref "R31") (pin "2") (pinfunction "2_2") (pintype "passive"))
      (node (ref "R33") (pin "2") (pinfunction "2_2") (pintype "passive"))
      (node (ref "R35") (pin "2") (pinfunction "2_2") (pintype "passive"))
      (node (ref "R37") (pin "2") (pinfunction "2_2") (pintype "passive"))
      (node (ref "R39") (pin "2") (pinfunction "2_2") (pintype "passive"))
      (node (ref "R41") (pin "2") (pinfunction "2_2") (pintype "passive"))
      (node (ref "R43") (pin "2") (pinfunction "2_2") (pintype "passive"))
      (node (ref "R45") (pin "2") (pinfunction "2_2") (pintype "passive"))
      (node (ref "R47") (pin "2") (pinfunction "2_2") (pintype "passive"))
      (node (ref "R49") (pin "2") (pinfunction "2_2") (pintype "passive"))
      (node (ref "R5") (pin "2") (pinfunction "2_2") (pintype "passive"))
      (node (ref "R51") (pin "2") (pinfunction "2_2") (pintype "passive"))
      (node (ref "R53") (pin "2") (pinfunction "2_2") (pintype "passive"))
      (node (ref "R55") (pin "2") (pinfunction "2_2") (pintype "passive"))
      (node (ref "R57") (pin "2") (pinfunction "2_2") (pintype "passive"))
      (node (ref "R59") (pin "2") (pinfunction "2_2") (pintype "passive"))
      (node (ref "R61") (pin "2") (pinfunction "2_2") (pintype "passive"))
      (node (ref "R63") (pin "2") (pinfunction "2_2") (pintype "passive"))
      (node (ref "R7") (pin "2") (pinfunction "2_2") (pintype "passive"))
      (node (ref "R9") (pin "2") (pinfunction "2_2") (pintype "passive"))
      (node (ref "S1") (pin "1") (pinfunction "1_1") (pintype "passive"))
      (node (ref "U2") (pin "23") (pinfunction "VSS_1_23") (pintype "power_in"))
      (node (ref "U2") (pin "35") (pinfunction "VSS_2_35") (pintype "power_in"))
      (node (ref "U2") (pin "47") (pinfunction "VSS_3_47") (pintype "power_in"))
      (node (ref "U2") (pin "8") (pinfunction "VSSA_8") (pintype "power_in"))
      (node (ref "U3") (pin "1") (pinfunction "GND_1") (pintype "passive"))
      (node (ref "Y3") (pin "2") (pinfunction "GND_2") (pintype "power_in"))
      (node (ref "Y3") (pin "4") (pinfunction "GND_4") (pintype "power_in"))
    )
    (net (code "42") (name "Net-(D1-PadA)") (class "Default")
      (node (ref "D1") (pin "A") (pinfunction "A_A") (pintype "passive"))
      (node (ref "R3") (pin "2") (pinfunction "2_2") (pintype "passive"))
    )
    (net (code "43") (name "Net-(U2A-BOOT0)") (class "Default")
      (node (ref "R1") (pin "1") (pinfunction "1_1") (pintype "passive"))
      (node (ref "U2") (pin "44") (pinfunction "BOOT0_44") (pintype "input"))
    )
    (net (code "44") (name "Net-(U2A-PD1-OSC_OUT)") (class "Default")
      (node (ref "R2") (pin "2") (pinfunction "2_2") (pintype "passive"))
      (node (ref "U2") (pin "6") (pinfunction "PD1-OSC_OUT_6") (pintype "bidirectional"))
    )
    (net (code "45") (name "unconnected-(U2A-PC13-TAMPER-RTC-Pad2)") (class "Default")
      (node (ref "U2") (pin "2") (pinfunction "PC13-TAMPER-RTC_2") (pintype "bidirectional+no_connect"))
    )
    (net (code "46") (name "unconnected-(U2B-VBAT-Pad1)") (class "Default")
      (node (ref "U2") (pin "1") (pinfunction "VBAT_1") (pintype "power_in"))
    )
  )
)
